# CH32V407VET-USB.net
KiCad netlist of a schematic drawn in Altium Designer
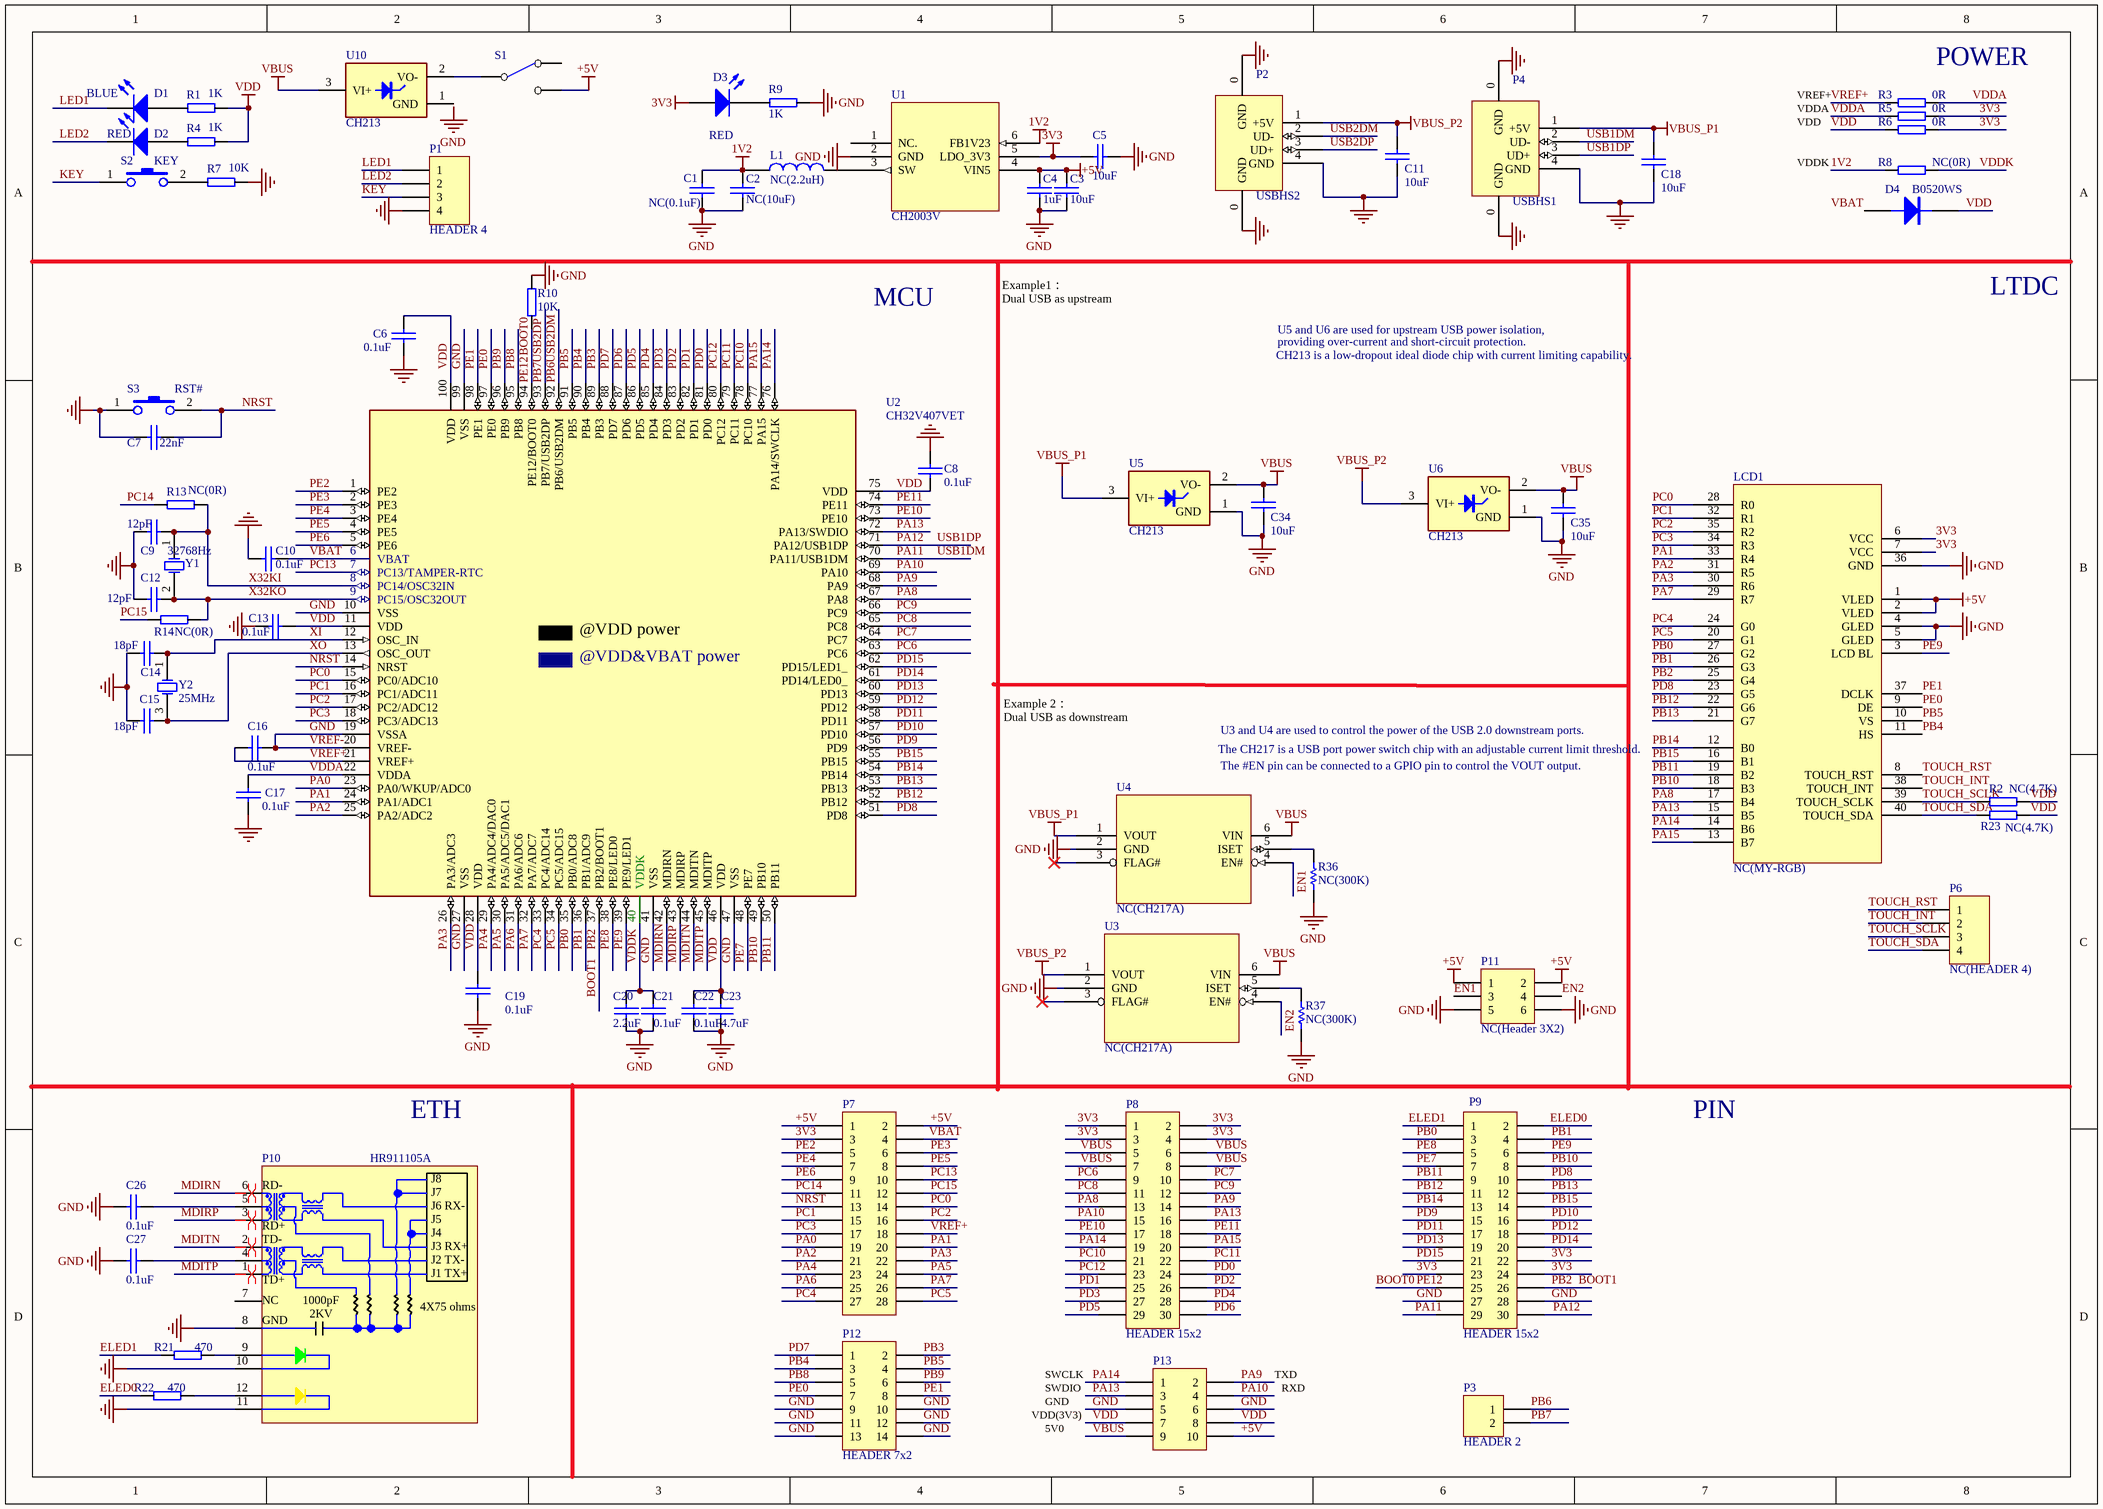
[diagram p0: CH32V407VET-USB.SchDoc]

(export (version "E")
  (design (tool "Eeschema 10.0.6"))
  (components
    (comp (ref "C1")
      (value "NC(0.1uF)")
      (footprint "0402_C")
      (description "Capacitor")
      (libsource (lib "") (part "CAP_1"))
    )
    (comp (ref "C2")
      (value "NC(10uF)")
      (footprint "0603_C")
      (description "Capacitor")
      (libsource (lib "*") (part "CAP"))
    )
    (comp (ref "C3")
      (value "10uF")
      (footprint "0603_C")
      (description "Capacitor")
      (libsource (lib "*") (part "CAP"))
    )
    (comp (ref "C4")
      (value "1uF")
      (footprint "0402_C")
      (description "Capacitor")
      (libsource (lib "") (part "CAP_1"))
    )
    (comp (ref "C5")
      (value "10uF")
      (footprint "0603_C")
      (description "Capacitor")
      (libsource (lib "*") (part "CAP"))
    )
    (comp (ref "C6")
      (value "0.1uF")
      (footprint "0402_C")
      (description "Capacitor")
      (libsource (lib "*") (part "CAP"))
    )
    (comp (ref "C7")
      (value "22nF")
      (footprint "0402_C")
      (description "Capacitor")
      (libsource (lib "") (part "CAP_2"))
    )
    (comp (ref "C8")
      (value "0.1uF")
      (footprint "0402_C")
      (description "Capacitor")
      (libsource (lib "*") (part "CAP"))
    )
    (comp (ref "C9")
      (value "12pF")
      (footprint "0402_C")
      (description "Capacitor")
      (libsource (lib "*") (part "CAP"))
    )
    (comp (ref "C10")
      (value "0.1uF")
      (footprint "0402_C")
      (description "Capacitor")
      (libsource (lib "*") (part "CAP"))
    )
    (comp (ref "C11")
      (value "10uF")
      (footprint "0603_C")
      (description "Capacitor")
      (libsource (lib "") (part "CAP_2"))
    )
    (comp (ref "C12")
      (value "12pF")
      (footprint "0402_C")
      (description "Capacitor")
      (libsource (lib "*") (part "CAP"))
    )
    (comp (ref "C13")
      (value "0.1uF")
      (footprint "0402_C")
      (description "Capacitor")
      (libsource (lib "*") (part "CAP"))
    )
    (comp (ref "C14")
      (value "18pF")
      (footprint "0402_C")
      (description "Capacitor")
      (libsource (lib "*") (part "CAP"))
    )
    (comp (ref "C15")
      (value "18pF")
      (footprint "0402_C")
      (description "Capacitor")
      (libsource (lib "*") (part "CAP"))
    )
    (comp (ref "C16")
      (value "0.1uF")
      (footprint "0402_C")
      (description "Capacitor")
      (libsource (lib "*") (part "CAP"))
    )
    (comp (ref "C17")
      (value "0.1uF")
      (footprint "0402_C")
      (description "Capacitor")
      (libsource (lib "*") (part "CAP"))
    )
    (comp (ref "C18")
      (value "10uF")
      (footprint "0603_C")
      (description "Capacitor")
      (libsource (lib "") (part "CAP_2"))
    )
    (comp (ref "C19")
      (value "0.1uF")
      (footprint "0402_C")
      (description "Capacitor")
      (libsource (lib "*") (part "CAP"))
    )
    (comp (ref "C20")
      (value "2.2uF")
      (footprint "0402_C")
      (description "Capacitor")
      (libsource (lib "*") (part "CAP"))
    )
    (comp (ref "C21")
      (value "0.1uF")
      (footprint "0402_C")
      (description "Capacitor")
      (libsource (lib "*") (part "CAP"))
    )
    (comp (ref "C22")
      (value "0.1uF")
      (footprint "0402_C")
      (description "Capacitor")
      (libsource (lib "*") (part "CAP"))
    )
    (comp (ref "C23")
      (value "4.7uF")
      (footprint "0402_C")
      (description "Capacitor")
      (libsource (lib "*") (part "CAP"))
    )
    (comp (ref "C26")
      (value "0.1uF")
      (footprint "0402_C")
      (description "Capacitor")
      (libsource (lib "wch_sch_others") (part "CAP"))
    )
    (comp (ref "C27")
      (value "0.1uF")
      (footprint "0402_C")
      (description "Capacitor")
      (libsource (lib "wch_sch_others") (part "CAP"))
    )
    (comp (ref "C34")
      (value "10uF")
      (footprint "0603_C")
      (description "Capacitor")
      (libsource (lib "") (part "CAP_2"))
    )
    (comp (ref "C35")
      (value "10uF")
      (footprint "0603_C")
      (description "Capacitor")
      (libsource (lib "") (part "CAP_2"))
    )
    (comp (ref "D1")
      (value "BLUE")
      (footprint "0603+")
      (description "Typical INFRARED GaAs LED")
      (fields (field (name "PUBLISHER") "Altium Limited"))
      (libsource (lib "*") (part "LED0"))
    )
    (comp (ref "D2")
      (value "RED")
      (footprint "0603+")
      (description "Typical INFRARED GaAs LED")
      (fields (field (name "PUBLISHER") "Altium Limited"))
      (libsource (lib "*") (part "LED0"))
    )
    (comp (ref "D3")
      (value "RED")
      (footprint "0603+")
      (description "Typical INFRARED GaAs LED")
      (fields (field (name "PUBLISHER") "Altium Limited"))
      (libsource (lib "*") (part "LED0"))
    )
    (comp (ref "D4")
      (value "B0520WS")
      (footprint "SOD-323")
      (description "Diode")
      (libsource (lib "*") (part "DIODE"))
    )
    (comp (ref "L1") (value "NC(2.2uH)") (footprint "CD32") (libsource (lib "*") (part "INDUCTOR")))
    (comp (ref "LCD1")
      (value "NC(MY-RGB)")
      (footprint "FPC40P-0.5-FK750M3")
      (libsource (lib "MY-显示") (part "MY-RGB"))
    )
    (comp (ref "P1")
      (value "HEADER 4")
      (footprint "SIP4-2.54mm")
      (description "Header, 4-Pin")
      (libsource (lib "wch_sch_others") (part "HEADER 4"))
    )
    (comp (ref "P2")
      (value "USBHS2")
      (footprint "USBAF")
      (description "USB Port")
      (libsource (lib "*") (part "USB"))
    )
    (comp (ref "P3")
      (value "HEADER 2")
      (footprint "MYPCB:SIP2-2.54mm")
      (description "Header, 2-Pin")
      (libsource (lib "wch_sch_others") (part "HEADER 2"))
    )
    (comp (ref "P4")
      (value "USBHS1")
      (footprint "USBAF")
      (description "USB Port")
      (libsource (lib "*") (part "USB"))
    )
    (comp (ref "P6")
      (value "NC(HEADER 4)")
      (footprint "SIP4-2.54mm")
      (description "Header, 4-Pin")
      (libsource (lib "wch_sch_others") (part "HEADER 4"))
    )
    (comp (ref "P7")
      (value "HEADER 14x2")
      (footprint "MYPCB:IDC28-2.54MM")
      (description "Header, 14-Pin, Dual row")
      (libsource (lib "wch_sch_others") (part "HEADER 14x2"))
    )
    (comp (ref "P8")
      (value "HEADER 15x2")
      (footprint "MYPCB:IDC30-2.54MM")
      (description "Header, 15-Pin, Dual row")
      (libsource (lib "wch_sch_others") (part "HEADER 15x2"))
    )
    (comp (ref "P9")
      (value "HEADER 15x2")
      (footprint "MYPCB:IDC30-2.54MM")
      (description "Header, 15-Pin, Dual row")
      (libsource (lib "wch_sch_others") (part "HEADER 15x2"))
    )
    (comp (ref "P10") (value "HR911105A") (footprint "HR911105A") (libsource (lib "*") (part "HR911105A")))
    (comp (ref "P11")
      (value "NC(Header 3X2)")
      (footprint "HDR2X3")
      (description "Header, 3-Pin, Dual row")
      (fields (field (name "PUBLISHER") "Altium Limited"))
      (libsource (lib "Miscellaneous Connectors") (part "Header 3X2"))
    )
    (comp (ref "P12")
      (value "HEADER 7x2")
      (footprint "MYPCB:IDC14-2.54mm")
      (description "Header, 7-Pin, Dual row")
      (libsource (lib "wch_sch_others") (part "HEADER 7x2"))
    )
    (comp (ref "P13")
      (value "LINK")
      (footprint "IDC10-2.54mm")
      (description "Header, 5-Pin, Dual row, Right Angle")
      (fields (field (name "PUBLISHER") "Altium Limited"))
      (libsource (lib "Miscellaneous Connectors") (part "Header 5X2H"))
    )
    (comp (ref "R1") (value "1K") (footprint "0402") (libsource (lib "wch_sch_others") (part "RES")))
    (comp (ref "R2") (value "NC(4.7K)") (footprint "0402") (libsource (lib "wch_sch_others") (part "RES")))
    (comp (ref "R3") (value "0R") (footprint "0402") (libsource (lib "*") (part "R")))
    (comp (ref "R4") (value "1K") (footprint "0402") (libsource (lib "wch_sch_others") (part "RES")))
    (comp (ref "R5") (value "0R") (footprint "0402") (libsource (lib "*") (part "R")))
    (comp (ref "R6") (value "0R") (footprint "0402") (libsource (lib "*") (part "R")))
    (comp (ref "R7") (value "10K") (footprint "0402") (libsource (lib "wch_sch_others") (part "RES")))
    (comp (ref "R8") (value "NC(0R)") (footprint "0402") (libsource (lib "*") (part "R")))
    (comp (ref "R9") (value "1K") (footprint "0402") (libsource (lib "wch_sch_others") (part "RES")))
    (comp (ref "R10") (value "10K") (footprint "0402") (libsource (lib "wch_sch_others") (part "RES")))
    (comp (ref "R13") (value "NC(0R)") (footprint "0402") (libsource (lib "wch_sch_others") (part "RES")))
    (comp (ref "R14") (value "NC(0R)") (footprint "0402") (libsource (lib "wch_sch_others") (part "RES")))
    (comp (ref "R21") (value "470") (footprint "0402") (libsource (lib "wch_sch_others") (part "RES")))
    (comp (ref "R22") (value "470") (footprint "0402") (libsource (lib "wch_sch_others") (part "RES")))
    (comp (ref "R23") (value "NC(4.7K)") (footprint "0402") (libsource (lib "wch_sch_others") (part "RES")))
    (comp (ref "R36")
      (value "NC(300K)")
      (footprint "0603")
      (description "Resistor")
      (fields (field (name "PUBLISHER") "Altium Limited"))
      (libsource (lib "MYLIB") (part "0603-1"))
    )
    (comp (ref "R37")
      (value "NC(300K)")
      (footprint "0603")
      (description "Resistor")
      (fields (field (name "PUBLISHER") "Altium Limited"))
      (libsource (lib "MYLIB") (part "0603-1"))
    )
    (comp (ref "S1") (value "SW SPDT") (footprint "SW1") (libsource (lib "*") (part "SW SPDT")))
    (comp (ref "S2")
      (value "KEY")
      (footprint "SMD_6.1x3.65x2.5mm-KEY")
      (libsource (lib "wch_sch_others") (part "KEY1"))
    )
    (comp (ref "S3")
      (value "RST#")
      (footprint "SMD_6.1x3.65x2.5mm-KEY")
      (libsource (lib "wch_sch_others") (part "KEY1"))
    )
    (comp (ref "U1")
      (value "CH2003V")
      (footprint "SOT-23-6")
      (description "Step-Down DC-DC Converter, 5V input, 1.23V * 800mA output, with LDO 3.3V * 200mA")
      (libsource (lib "CHXXX") (part "CH2003V"))
    )
    (comp (ref "U2")
      (value "CH32V407VET")
      (footprint "LQFP100")
      (description "RISC-V FPU HD-MCU, 175MHz, USB_480M, 100M Ethernet & Phy, CAN, DVP, ADC, DAC")
      (libsource (lib "CHXXX") (part "CH32V407VET"))
    )
    (comp (ref "U3")
      (value "NC(CH217A)")
      (footprint "SOT-23-6")
      (description "Current-Limited USB Power Distribution Switch")
      (libsource (lib "CHXXX") (part "CH217K"))
    )
    (comp (ref "U4")
      (value "NC(CH217A)")
      (footprint "SOT-23-6")
      (description "Current-Limited USB Power Distribution Switch")
      (libsource (lib "CHXXX") (part "CH217K"))
    )
    (comp (ref "U5")
      (value "CH213")
      (footprint "SOT-23-3")
      (description "Ideal Diode 5V*1A")
      (libsource (lib "CHXXX") (part "CH213E"))
    )
    (comp (ref "U6")
      (value "CH213")
      (footprint "SOT-23-3")
      (description "Ideal Diode 5V*1A")
      (libsource (lib "CHXXX") (part "CH213E"))
    )
    (comp (ref "U10")
      (value "CH213")
      (footprint "SOT-23-3")
      (description "Ideal Diode 5V*1A")
      (libsource (lib "CHXXX") (part "CH213E"))
    )
    (comp (ref "Y1")
      (value "32768Hz")
      (footprint "FC-135")
      (description "Crystal Oscillator")
      (fields (field (name "PUBLISHER") "Altium Limited"))
      (libsource (lib "*") (part "XTAL"))
    )
    (comp (ref "Y2")
      (value "25MHz")
      (footprint "XT3225")
      (description "Crystal Oscillator")
      (fields (field (name "PUBLISHER") "Altium Limited"))
      (libsource (lib "") (part "XTAL_1"))
    )
  )
  (nets
    (net (code "1") (name "+5V") (class "Default")
      (node (ref "C3") (pin "2") (pinfunction "2_2") (pintype "passive"))
      (node (ref "C4") (pin "2") (pinfunction "2_2") (pintype "passive"))
      (node (ref "LCD1") (pin "1") (pinfunction "VLED_1") (pintype "passive"))
      (node (ref "LCD1") (pin "2") (pinfunction "VLED_2") (pintype "passive"))
      (node (ref "P11") (pin "1") (pinfunction "1_1") (pintype "passive"))
      (node (ref "P11") (pin "2") (pinfunction "2_2") (pintype "passive"))
      (node (ref "P13") (pin "10") (pinfunction "10_10") (pintype "passive"))
      (node (ref "P7") (pin "1") (pinfunction "1_1") (pintype "passive"))
      (node (ref "P7") (pin "2") (pinfunction "2_2") (pintype "passive"))
      (node (ref "S1") (pin "2") (pinfunction "NC_2") (pintype "passive"))
      (node (ref "U1") (pin "4") (pinfunction "VIN5_4") (pintype "power_in"))
    )
    (net (code "3") (name "/BOOT0") (class "Default")
      (node (ref "P9") (pin "25") (pinfunction "25_25") (pintype "passive"))
      (node (ref "R10") (pin "2") (pintype "passive"))
      (node (ref "U2") (pin "94") (pinfunction "PE12/BOOT0_94") (pintype "bidirectional"))
    )
    (net (code "4") (name "/BOOT1") (class "Default")
      (node (ref "LCD1") (pin "25") (pinfunction "G4_25") (pintype "passive"))
      (node (ref "P9") (pin "26") (pinfunction "26_26") (pintype "passive"))
      (node (ref "U2") (pin "37") (pinfunction "PB2/BOOT1_37") (pintype "bidirectional"))
    )
    (net (code "5") (name "/ELED0") (class "Default")
      (node (ref "P9") (pin "2") (pinfunction "2_2") (pintype "passive"))
      (node (ref "R22") (pin "1") (pintype "passive"))
    )
    (net (code "6") (name "/ELED1") (class "Default")
      (node (ref "P9") (pin "1") (pinfunction "1_1") (pintype "passive"))
      (node (ref "R21") (pin "1") (pintype "passive"))
    )
    (net (code "7") (name "/EN1") (class "Default")
      (node (ref "P11") (pin "3") (pinfunction "3_3") (pintype "passive"))
      (node (ref "U4") (pin "4") (pinfunction "EN#_4") (pintype "input"))
    )
    (net (code "8") (name "/EN2") (class "Default")
      (node (ref "P11") (pin "4") (pinfunction "4_4") (pintype "passive"))
      (node (ref "U3") (pin "4") (pinfunction "EN#_4") (pintype "input"))
    )
    (net (code "9") (name "/KEY") (class "Default")
      (node (ref "P1") (pin "3") (pinfunction "3_3") (pintype "passive"))
      (node (ref "S2") (pin "1") (pinfunction "1_1") (pintype "passive"))
    )
    (net (code "10") (name "/LED1") (class "Default")
      (node (ref "D1") (pin "2") (pinfunction "K_2") (pintype "passive"))
      (node (ref "P1") (pin "1") (pinfunction "1_1") (pintype "passive"))
    )
    (net (code "11") (name "/LED2") (class "Default")
      (node (ref "D2") (pin "2") (pinfunction "K_2") (pintype "passive"))
      (node (ref "P1") (pin "2") (pinfunction "2_2") (pintype "passive"))
    )
    (net (code "12") (name "/MDIRN") (class "Default")
      (node (ref "P10") (pin "6") (pintype "passive"))
      (node (ref "U2") (pin "42") (pinfunction "MDIRN_42") (pintype "bidirectional"))
    )
    (net (code "13") (name "/MDIRP") (class "Default")
      (node (ref "P10") (pin "3") (pintype "passive"))
      (node (ref "U2") (pin "43") (pinfunction "MDIRP_43") (pintype "bidirectional"))
    )
    (net (code "14") (name "/MDITN") (class "Default")
      (node (ref "P10") (pin "2") (pintype "passive"))
      (node (ref "U2") (pin "44") (pinfunction "MDITN_44") (pintype "bidirectional"))
    )
    (net (code "15") (name "/MDITP") (class "Default")
      (node (ref "P10") (pin "1") (pintype "passive"))
      (node (ref "U2") (pin "45") (pinfunction "MDITP_45") (pintype "bidirectional"))
    )
    (net (code "16") (name "/NRST") (class "Default")
      (node (ref "C7") (pin "2") (pinfunction "2_2") (pintype "passive"))
      (node (ref "P7") (pin "13") (pinfunction "13_13") (pintype "passive"))
      (node (ref "S3") (pin "2") (pinfunction "2_2") (pintype "passive"))
      (node (ref "U2") (pin "14") (pinfunction "NRST_14") (pintype "input"))
    )
    (net (code "17") (name "/PA0") (class "Default")
      (node (ref "P7") (pin "19") (pinfunction "19_19") (pintype "passive"))
      (node (ref "U2") (pin "23") (pinfunction "PA0/WKUP/ADC0_23") (pintype "bidirectional"))
    )
    (net (code "18") (name "/PA1") (class "Default")
      (node (ref "LCD1") (pin "33") (pinfunction "R4_33") (pintype "passive"))
      (node (ref "P7") (pin "20") (pinfunction "20_20") (pintype "passive"))
      (node (ref "U2") (pin "24") (pinfunction "PA1/ADC1_24") (pintype "bidirectional"))
    )
    (net (code "19") (name "/PA2") (class "Default")
      (node (ref "LCD1") (pin "31") (pinfunction "R5_31") (pintype "passive"))
      (node (ref "P7") (pin "21") (pinfunction "21_21") (pintype "passive"))
      (node (ref "U2") (pin "25") (pinfunction "PA2/ADC2_25") (pintype "bidirectional"))
    )
    (net (code "20") (name "/PA3") (class "Default")
      (node (ref "LCD1") (pin "30") (pinfunction "R6_30") (pintype "passive"))
      (node (ref "P7") (pin "22") (pinfunction "22_22") (pintype "passive"))
      (node (ref "U2") (pin "26") (pinfunction "PA3/ADC3_26") (pintype "bidirectional"))
    )
    (net (code "21") (name "/PA4") (class "Default")
      (node (ref "P7") (pin "23") (pinfunction "23_23") (pintype "passive"))
      (node (ref "U2") (pin "29") (pinfunction "PA4/ADC4/DAC0_29") (pintype "bidirectional"))
    )
    (net (code "22") (name "/PA5") (class "Default")
      (node (ref "P7") (pin "24") (pinfunction "24_24") (pintype "passive"))
      (node (ref "U2") (pin "30") (pinfunction "PA5/ADC5/DAC1_30") (pintype "bidirectional"))
    )
    (net (code "23") (name "/PA6") (class "Default")
      (node (ref "P7") (pin "25") (pinfunction "25_25") (pintype "passive"))
      (node (ref "U2") (pin "31") (pinfunction "PA6/ADC6_31") (pintype "bidirectional"))
    )
    (net (code "24") (name "/PA7") (class "Default")
      (node (ref "LCD1") (pin "29") (pinfunction "R7_29") (pintype "passive"))
      (node (ref "P7") (pin "26") (pinfunction "26_26") (pintype "passive"))
      (node (ref "U2") (pin "32") (pinfunction "PA7/ADC7_32") (pintype "bidirectional"))
    )
    (net (code "25") (name "/PA8") (class "Default")
      (node (ref "LCD1") (pin "17") (pinfunction "B4_17") (pintype "passive"))
      (node (ref "P8") (pin "13") (pinfunction "13_13") (pintype "passive"))
      (node (ref "U2") (pin "67") (pinfunction "PA8_67") (pintype "bidirectional"))
    )
    (net (code "26") (name "/PA9") (class "Default")
      (node (ref "P13") (pin "2") (pinfunction "2_2") (pintype "passive"))
      (node (ref "P8") (pin "14") (pinfunction "14_14") (pintype "passive"))
      (node (ref "U2") (pin "68") (pinfunction "PA9_68") (pintype "bidirectional"))
    )
    (net (code "27") (name "/PA10") (class "Default")
      (node (ref "P13") (pin "4") (pinfunction "4_4") (pintype "passive"))
      (node (ref "P8") (pin "15") (pinfunction "15_15") (pintype "passive"))
      (node (ref "U2") (pin "69") (pinfunction "PA10_69") (pintype "bidirectional"))
    )
    (net (code "28") (name "/PA11") (class "Default")
      (node (ref "P4") (pin "2") (pinfunction "UD-_2") (pintype "bidirectional"))
      (node (ref "P9") (pin "29") (pinfunction "29_29") (pintype "passive"))
      (node (ref "U2") (pin "70") (pinfunction "PA11/USB1DM_70") (pintype "bidirectional"))
    )
    (net (code "29") (name "/PA12") (class "Default")
      (node (ref "P4") (pin "3") (pinfunction "UD+_3") (pintype "bidirectional"))
      (node (ref "P9") (pin "30") (pinfunction "30_30") (pintype "passive"))
      (node (ref "U2") (pin "71") (pinfunction "PA12/USB1DP_71") (pintype "bidirectional"))
    )
    (net (code "30") (name "/PA13") (class "Default")
      (node (ref "LCD1") (pin "15") (pinfunction "B5_15") (pintype "passive"))
      (node (ref "P13") (pin "3") (pinfunction "3_3") (pintype "passive"))
      (node (ref "P8") (pin "16") (pinfunction "16_16") (pintype "passive"))
      (node (ref "U2") (pin "72") (pinfunction "PA13/SWDIO_72") (pintype "bidirectional"))
    )
    (net (code "31") (name "/PA14") (class "Default")
      (node (ref "LCD1") (pin "14") (pinfunction "B6_14") (pintype "passive"))
      (node (ref "P13") (pin "1") (pinfunction "1_1") (pintype "passive"))
      (node (ref "P8") (pin "19") (pinfunction "19_19") (pintype "passive"))
      (node (ref "U2") (pin "76") (pinfunction "PA14/SWCLK_76") (pintype "bidirectional"))
    )
    (net (code "32") (name "/PA15") (class "Default")
      (node (ref "LCD1") (pin "13") (pinfunction "B7_13") (pintype "passive"))
      (node (ref "P8") (pin "20") (pinfunction "20_20") (pintype "passive"))
      (node (ref "U2") (pin "77") (pinfunction "PA15_77") (pintype "bidirectional"))
    )
    (net (code "33") (name "/PB0") (class "Default")
      (node (ref "LCD1") (pin "27") (pinfunction "G2_27") (pintype "passive"))
      (node (ref "P9") (pin "3") (pinfunction "3_3") (pintype "passive"))
      (node (ref "U2") (pin "35") (pinfunction "PB0/ADC8_35") (pintype "bidirectional"))
    )
    (net (code "34") (name "/PB1") (class "Default")
      (node (ref "LCD1") (pin "26") (pinfunction "G3_26") (pintype "passive"))
      (node (ref "P9") (pin "4") (pinfunction "4_4") (pintype "passive"))
      (node (ref "U2") (pin "36") (pinfunction "PB1/ADC9_36") (pintype "bidirectional"))
    )
    (net (code "35") (name "/PB3") (class "Default")
      (node (ref "P12") (pin "2") (pinfunction "2_2") (pintype "passive"))
      (node (ref "U2") (pin "89") (pinfunction "PB3_89") (pintype "bidirectional"))
    )
    (net (code "36") (name "/PB4") (class "Default")
      (node (ref "LCD1") (pin "11") (pinfunction "HS_11") (pintype "passive"))
      (node (ref "P12") (pin "3") (pinfunction "3_3") (pintype "passive"))
      (node (ref "U2") (pin "90") (pinfunction "PB4_90") (pintype "bidirectional"))
    )
    (net (code "37") (name "/PB5") (class "Default")
      (node (ref "LCD1") (pin "10") (pinfunction "VS_10") (pintype "passive"))
      (node (ref "P12") (pin "4") (pinfunction "4_4") (pintype "passive"))
      (node (ref "U2") (pin "91") (pinfunction "PB5_91") (pintype "bidirectional"))
    )
    (net (code "38") (name "/PB6") (class "Default")
      (node (ref "P2") (pin "2") (pinfunction "UD-_2") (pintype "bidirectional"))
      (node (ref "P3") (pin "1") (pinfunction "1_1") (pintype "passive"))
      (node (ref "U2") (pin "92") (pinfunction "PB6/USB2DM_92") (pintype "bidirectional"))
    )
    (net (code "39") (name "/PB7") (class "Default")
      (node (ref "P2") (pin "3") (pinfunction "UD+_3") (pintype "bidirectional"))
      (node (ref "P3") (pin "2") (pinfunction "2_2") (pintype "passive"))
      (node (ref "U2") (pin "93") (pinfunction "PB7/USB2DP_93") (pintype "bidirectional"))
    )
    (net (code "40") (name "/PB8") (class "Default")
      (node (ref "P12") (pin "5") (pinfunction "5_5") (pintype "passive"))
      (node (ref "U2") (pin "95") (pinfunction "PB8_95") (pintype "bidirectional"))
    )
    (net (code "41") (name "/PB9") (class "Default")
      (node (ref "P12") (pin "6") (pinfunction "6_6") (pintype "passive"))
      (node (ref "U2") (pin "96") (pinfunction "PB9_96") (pintype "bidirectional"))
    )
    (net (code "42") (name "/PB10") (class "Default")
      (node (ref "LCD1") (pin "18") (pinfunction "B3_18") (pintype "passive"))
      (node (ref "P9") (pin "8") (pinfunction "8_8") (pintype "passive"))
      (node (ref "U2") (pin "49") (pinfunction "PB10_49") (pintype "bidirectional"))
    )
    (net (code "43") (name "/PB11") (class "Default")
      (node (ref "LCD1") (pin "19") (pinfunction "B2_19") (pintype "passive"))
      (node (ref "P9") (pin "9") (pinfunction "9_9") (pintype "passive"))
      (node (ref "U2") (pin "50") (pinfunction "PB11_50") (pintype "bidirectional"))
    )
    (net (code "44") (name "/PB12") (class "Default")
      (node (ref "LCD1") (pin "22") (pinfunction "G6_22") (pintype "passive"))
      (node (ref "P9") (pin "11") (pinfunction "11_11") (pintype "passive"))
      (node (ref "U2") (pin "52") (pinfunction "PB12_52") (pintype "bidirectional"))
    )
    (net (code "45") (name "/PB13") (class "Default")
      (node (ref "LCD1") (pin "21") (pinfunction "G7_21") (pintype "passive"))
      (node (ref "P9") (pin "12") (pinfunction "12_12") (pintype "passive"))
      (node (ref "U2") (pin "53") (pinfunction "PB13_53") (pintype "bidirectional"))
    )
    (net (code "46") (name "/PB14") (class "Default")
      (node (ref "LCD1") (pin "12") (pinfunction "B0_12") (pintype "passive"))
      (node (ref "P9") (pin "13") (pinfunction "13_13") (pintype "passive"))
      (node (ref "U2") (pin "54") (pinfunction "PB14_54") (pintype "bidirectional"))
    )
    (net (code "47") (name "/PB15") (class "Default")
      (node (ref "LCD1") (pin "16") (pinfunction "B1_16") (pintype "passive"))
      (node (ref "P9") (pin "14") (pinfunction "14_14") (pintype "passive"))
      (node (ref "U2") (pin "55") (pinfunction "PB15_55") (pintype "bidirectional"))
    )
    (net (code "48") (name "/PC0") (class "Default")
      (node (ref "LCD1") (pin "28") (pinfunction "R0_28") (pintype "passive"))
      (node (ref "P7") (pin "14") (pinfunction "14_14") (pintype "passive"))
      (node (ref "U2") (pin "15") (pinfunction "PC0/ADC10_15") (pintype "bidirectional"))
    )
    (net (code "49") (name "/PC1") (class "Default")
      (node (ref "LCD1") (pin "32") (pinfunction "R1_32") (pintype "passive"))
      (node (ref "P7") (pin "15") (pinfunction "15_15") (pintype "passive"))
      (node (ref "U2") (pin "16") (pinfunction "PC1/ADC11_16") (pintype "bidirectional"))
    )
    (net (code "50") (name "/PC2") (class "Default")
      (node (ref "LCD1") (pin "35") (pinfunction "R2_35") (pintype "passive"))
      (node (ref "P7") (pin "16") (pinfunction "16_16") (pintype "passive"))
      (node (ref "U2") (pin "17") (pinfunction "PC2/ADC12_17") (pintype "bidirectional"))
    )
    (net (code "51") (name "/PC3") (class "Default")
      (node (ref "LCD1") (pin "34") (pinfunction "R3_34") (pintype "passive"))
      (node (ref "P7") (pin "17") (pinfunction "17_17") (pintype "passive"))
      (node (ref "U2") (pin "18") (pinfunction "PC3/ADC13_18") (pintype "bidirectional"))
    )
    (net (code "52") (name "/PC4") (class "Default")
      (node (ref "LCD1") (pin "24") (pinfunction "G0_24") (pintype "passive"))
      (node (ref "P7") (pin "27") (pinfunction "27_27") (pintype "passive"))
      (node (ref "U2") (pin "33") (pinfunction "PC4/ADC14_33") (pintype "bidirectional"))
    )
    (net (code "53") (name "/PC5") (class "Default")
      (node (ref "LCD1") (pin "20") (pinfunction "G1_20") (pintype "passive"))
      (node (ref "P7") (pin "28") (pinfunction "28_28") (pintype "passive"))
      (node (ref "U2") (pin "34") (pinfunction "PC5/ADC15_34") (pintype "bidirectional"))
    )
    (net (code "54") (name "/PC6") (class "Default")
      (node (ref "P8") (pin "9") (pinfunction "9_9") (pintype "passive"))
      (node (ref "U2") (pin "63") (pinfunction "PC6_63") (pintype "bidirectional"))
    )
    (net (code "55") (name "/PC7") (class "Default")
      (node (ref "P8") (pin "10") (pinfunction "10_10") (pintype "passive"))
      (node (ref "U2") (pin "64") (pinfunction "PC7_64") (pintype "bidirectional"))
    )
    (net (code "56") (name "/PC8") (class "Default")
      (node (ref "P8") (pin "11") (pinfunction "11_11") (pintype "passive"))
      (node (ref "U2") (pin "65") (pinfunction "PC8_65") (pintype "bidirectional"))
    )
    (net (code "57") (name "/PC9") (class "Default")
      (node (ref "P8") (pin "12") (pinfunction "12_12") (pintype "passive"))
      (node (ref "U2") (pin "66") (pinfunction "PC9_66") (pintype "bidirectional"))
    )
    (net (code "58") (name "/PC10") (class "Default")
      (node (ref "P8") (pin "21") (pinfunction "21_21") (pintype "passive"))
      (node (ref "U2") (pin "78") (pinfunction "PC10_78") (pintype "bidirectional"))
    )
    (net (code "59") (name "/PC11") (class "Default")
      (node (ref "P8") (pin "22") (pinfunction "22_22") (pintype "passive"))
      (node (ref "U2") (pin "79") (pinfunction "PC11_79") (pintype "bidirectional"))
    )
    (net (code "60") (name "/PC12") (class "Default")
      (node (ref "P8") (pin "23") (pinfunction "23_23") (pintype "passive"))
      (node (ref "U2") (pin "80") (pinfunction "PC12_80") (pintype "bidirectional"))
    )
    (net (code "61") (name "/PC13") (class "Default")
      (node (ref "P7") (pin "10") (pinfunction "10_10") (pintype "passive"))
      (node (ref "U2") (pin "7") (pinfunction "PC13/TAMPER-RTC_7") (pintype "bidirectional"))
    )
    (net (code "62") (name "/PC14") (class "Default")
      (node (ref "P7") (pin "11") (pinfunction "11_11") (pintype "passive"))
      (node (ref "R13") (pin "1") (pintype "passive"))
    )
    (net (code "63") (name "/PC15") (class "Default")
      (node (ref "P7") (pin "12") (pinfunction "12_12") (pintype "passive"))
      (node (ref "R14") (pin "1") (pintype "passive"))
    )
    (net (code "64") (name "/PD0") (class "Default")
      (node (ref "P8") (pin "24") (pinfunction "24_24") (pintype "passive"))
      (node (ref "U2") (pin "81") (pinfunction "PD0_81") (pintype "bidirectional"))
    )
    (net (code "65") (name "/PD1") (class "Default")
      (node (ref "P8") (pin "25") (pinfunction "25_25") (pintype "passive"))
      (node (ref "U2") (pin "82") (pinfunction "PD1_82") (pintype "bidirectional"))
    )
    (net (code "66") (name "/PD2") (class "Default")
      (node (ref "P8") (pin "26") (pinfunction "26_26") (pintype "passive"))
      (node (ref "U2") (pin "83") (pinfunction "PD2_83") (pintype "bidirectional"))
    )
    (net (code "67") (name "/PD3") (class "Default")
      (node (ref "P8") (pin "27") (pinfunction "27_27") (pintype "passive"))
      (node (ref "U2") (pin "84") (pinfunction "PD3_84") (pintype "bidirectional"))
    )
    (net (code "68") (name "/PD4") (class "Default")
      (node (ref "P8") (pin "28") (pinfunction "28_28") (pintype "passive"))
      (node (ref "U2") (pin "85") (pinfunction "PD4_85") (pintype "bidirectional"))
    )
    (net (code "69") (name "/PD5") (class "Default")
      (node (ref "P8") (pin "29") (pinfunction "29_29") (pintype "passive"))
      (node (ref "U2") (pin "86") (pinfunction "PD5_86") (pintype "bidirectional"))
    )
    (net (code "70") (name "/PD6") (class "Default")
      (node (ref "P8") (pin "30") (pinfunction "30_30") (pintype "passive"))
      (node (ref "U2") (pin "87") (pinfunction "PD6_87") (pintype "bidirectional"))
    )
    (net (code "71") (name "/PD7") (class "Default")
      (node (ref "P12") (pin "1") (pinfunction "1_1") (pintype "passive"))
      (node (ref "U2") (pin "88") (pinfunction "PD7_88") (pintype "bidirectional"))
    )
    (net (code "72") (name "/PD8") (class "Default")
      (node (ref "LCD1") (pin "23") (pinfunction "G5_23") (pintype "passive"))
      (node (ref "P9") (pin "10") (pinfunction "10_10") (pintype "passive"))
      (node (ref "U2") (pin "51") (pinfunction "PD8_51") (pintype "bidirectional"))
    )
    (net (code "73") (name "/PD9") (class "Default")
      (node (ref "P9") (pin "15") (pinfunction "15_15") (pintype "passive"))
      (node (ref "U2") (pin "56") (pinfunction "PD9_56") (pintype "bidirectional"))
    )
    (net (code "74") (name "/PD10") (class "Default")
      (node (ref "P9") (pin "16") (pinfunction "16_16") (pintype "passive"))
      (node (ref "U2") (pin "57") (pinfunction "PD10_57") (pintype "bidirectional"))
    )
    (net (code "75") (name "/PD11") (class "Default")
      (node (ref "P9") (pin "17") (pinfunction "17_17") (pintype "passive"))
      (node (ref "U2") (pin "58") (pinfunction "PD11_58") (pintype "bidirectional"))
    )
    (net (code "76") (name "/PD12") (class "Default")
      (node (ref "P9") (pin "18") (pinfunction "18_18") (pintype "passive"))
      (node (ref "U2") (pin "59") (pinfunction "PD12_59") (pintype "bidirectional"))
    )
    (net (code "77") (name "/PD13") (class "Default")
      (node (ref "P9") (pin "19") (pinfunction "19_19") (pintype "passive"))
      (node (ref "U2") (pin "60") (pinfunction "PD13_60") (pintype "bidirectional"))
    )
    (net (code "78") (name "/PD14") (class "Default")
      (node (ref "P9") (pin "20") (pinfunction "20_20") (pintype "passive"))
      (node (ref "U2") (pin "61") (pinfunction "PD14/LED0__61") (pintype "bidirectional"))
    )
    (net (code "79") (name "/PD15") (class "Default")
      (node (ref "P9") (pin "21") (pinfunction "21_21") (pintype "passive"))
      (node (ref "U2") (pin "62") (pinfunction "PD15/LED1__62") (pintype "bidirectional"))
    )
    (net (code "80") (name "/PE0") (class "Default")
      (node (ref "LCD1") (pin "9") (pinfunction "DE_9") (pintype "passive"))
      (node (ref "P12") (pin "7") (pinfunction "7_7") (pintype "passive"))
      (node (ref "U2") (pin "97") (pinfunction "PE0_97") (pintype "bidirectional"))
    )
    (net (code "81") (name "/PE1") (class "Default")
      (node (ref "LCD1") (pin "37") (pinfunction "DCLK_37") (pintype "passive"))
      (node (ref "P12") (pin "8") (pinfunction "8_8") (pintype "passive"))
      (node (ref "U2") (pin "98") (pinfunction "PE1_98") (pintype "bidirectional"))
    )
    (net (code "82") (name "/PE2") (class "Default")
      (node (ref "P7") (pin "5") (pinfunction "5_5") (pintype "passive"))
      (node (ref "U2") (pin "1") (pinfunction "PE2_1") (pintype "bidirectional"))
    )
    (net (code "83") (name "/PE3") (class "Default")
      (node (ref "P7") (pin "6") (pinfunction "6_6") (pintype "passive"))
      (node (ref "U2") (pin "2") (pinfunction "PE3_2") (pintype "bidirectional"))
    )
    (net (code "84") (name "/PE4") (class "Default")
      (node (ref "P7") (pin "7") (pinfunction "7_7") (pintype "passive"))
      (node (ref "U2") (pin "3") (pinfunction "PE4_3") (pintype "bidirectional"))
    )
    (net (code "85") (name "/PE5") (class "Default")
      (node (ref "P7") (pin "8") (pinfunction "8_8") (pintype "passive"))
      (node (ref "U2") (pin "4") (pinfunction "PE5_4") (pintype "bidirectional"))
    )
    (net (code "86") (name "/PE6") (class "Default")
      (node (ref "P7") (pin "9") (pinfunction "9_9") (pintype "passive"))
      (node (ref "U2") (pin "5") (pinfunction "PE6_5") (pintype "bidirectional"))
    )
    (net (code "87") (name "/PE7") (class "Default")
      (node (ref "P9") (pin "7") (pinfunction "7_7") (pintype "passive"))
      (node (ref "U2") (pin "48") (pinfunction "PE7_48") (pintype "bidirectional"))
    )
    (net (code "88") (name "/PE8") (class "Default")
      (node (ref "P9") (pin "5") (pinfunction "5_5") (pintype "passive"))
      (node (ref "U2") (pin "38") (pinfunction "PE8/LED0_38") (pintype "bidirectional"))
    )
    (net (code "89") (name "/PE9") (class "Default")
      (node (ref "LCD1") (pin "3") (pinfunction "LCD_BL_3") (pintype "passive"))
      (node (ref "P9") (pin "6") (pinfunction "6_6") (pintype "passive"))
      (node (ref "U2") (pin "39") (pinfunction "PE9/LED1_39") (pintype "bidirectional"))
    )
    (net (code "90") (name "/PE10") (class "Default")
      (node (ref "P8") (pin "17") (pinfunction "17_17") (pintype "passive"))
      (node (ref "U2") (pin "73") (pinfunction "PE10_73") (pintype "bidirectional"))
    )
    (net (code "91") (name "/PE11") (class "Default")
      (node (ref "P8") (pin "18") (pinfunction "18_18") (pintype "passive"))
      (node (ref "U2") (pin "74") (pinfunction "PE11_74") (pintype "bidirectional"))
    )
    (net (code "92") (name "/TOUCH_INT") (class "Default")
      (node (ref "LCD1") (pin "38") (pinfunction "TOUCH_INT_38") (pintype "passive"))
      (node (ref "P6") (pin "2") (pinfunction "2_2") (pintype "passive"))
    )
    (net (code "93") (name "/TOUCH_RST") (class "Default")
      (node (ref "LCD1") (pin "8") (pinfunction "TOUCH_RST_8") (pintype "passive"))
      (node (ref "P6") (pin "1") (pinfunction "1_1") (pintype "passive"))
    )
    (net (code "94") (name "/TOUCH_SCLK") (class "Default")
      (node (ref "LCD1") (pin "39") (pinfunction "TOUCH_SCLK_39") (pintype "passive"))
      (node (ref "P6") (pin "3") (pinfunction "3_3") (pintype "passive"))
      (node (ref "R2") (pin "2") (pintype "passive"))
    )
    (net (code "95") (name "/TOUCH_SDA") (class "Default")
      (node (ref "LCD1") (pin "40") (pinfunction "TOUCH_SDA_40") (pintype "passive"))
      (node (ref "P6") (pin "4") (pinfunction "4_4") (pintype "passive"))
      (node (ref "R23") (pin "2") (pintype "passive"))
    )
    (net (code "96") (name "/VBAT") (class "Default")
      (node (ref "C10") (pin "2") (pinfunction "2_2") (pintype "passive"))
      (node (ref "P7") (pin "4") (pinfunction "4_4") (pintype "passive"))
      (node (ref "U2") (pin "6") (pinfunction "VBAT_6") (pintype "power_in"))
    )
    (net (code "97") (name "/VDDA") (class "Default")
      (node (ref "C17") (pin "1") (pinfunction "1_1") (pintype "passive"))
      (node (ref "R3") (pin "1") (pinfunction "1_1") (pintype "passive"))
      (node (ref "R5") (pin "2") (pinfunction "2_2") (pintype "passive"))
      (node (ref "U2") (pin "22") (pinfunction "VDDA_22") (pintype "power_in"))
    )
    (net (code "98") (name "/VDDK") (class "Default")
      (node (ref "C20") (pin "2") (pinfunction "2_2") (pintype "passive"))
      (node (ref "C21") (pin "2") (pinfunction "2_2") (pintype "passive"))
      (node (ref "R8") (pin "1") (pinfunction "1_1") (pintype "passive"))
      (node (ref "U2") (pin "40") (pinfunction "VDDK_40") (pintype "power_in"))
    )
    (net (code "99") (name "/VREF+") (class "Default")
      (node (ref "C16") (pin "1") (pinfunction "1_1") (pintype "passive"))
      (node (ref "P7") (pin "18") (pinfunction "18_18") (pintype "passive"))
      (node (ref "R3") (pin "2") (pinfunction "2_2") (pintype "passive"))
      (node (ref "U2") (pin "21") (pinfunction "VREF+_21") (pintype "power_in"))
    )
    (net (code "100") (name "/X32KI") (class "Default")
      (node (ref "C9") (pin "2") (pinfunction "2_2") (pintype "passive"))
      (node (ref "R13") (pin "2") (pintype "passive"))
      (node (ref "U2") (pin "8") (pinfunction "PC14/OSC32IN_8") (pintype "bidirectional"))
      (node (ref "Y1") (pin "1") (pinfunction "OSC1_1") (pintype "passive"))
    )
    (net (code "101") (name "/X32KO") (class "Default")
      (node (ref "C12") (pin "2") (pinfunction "2_2") (pintype "passive"))
      (node (ref "R14") (pin "2") (pintype "passive"))
      (node (ref "U2") (pin "9") (pinfunction "PC15/OSC32OUT_9") (pintype "bidirectional"))
      (node (ref "Y1") (pin "2") (pinfunction "OSC2_2") (pintype "passive"))
    )
    (net (code "102") (name "/XI") (class "Default")
      (node (ref "C14") (pin "2") (pinfunction "2_2") (pintype "passive"))
      (node (ref "U2") (pin "12") (pinfunction "OSC_IN_12") (pintype "input"))
      (node (ref "Y2") (pin "1") (pinfunction "OSC1_1") (pintype "passive"))
    )
    (net (code "103") (name "/XO") (class "Default")
      (node (ref "C15") (pin "2") (pinfunction "2_2") (pintype "passive"))
      (node (ref "U2") (pin "13") (pinfunction "OSC_OUT_13") (pintype "output"))
      (node (ref "Y2") (pin "3") (pinfunction "OSC2_3") (pintype "passive"))
    )
    (net (code "104") (name "1V2") (class "Default")
      (node (ref "C1") (pin "2") (pinfunction "2_2") (pintype "passive"))
      (node (ref "C2") (pin "2") (pinfunction "2_2") (pintype "passive"))
      (node (ref "L1") (pin "2") (pinfunction "2_2") (pintype "passive"))
      (node (ref "R8") (pin "2") (pinfunction "2_2") (pintype "passive"))
      (node (ref "U1") (pin "6") (pinfunction "FB1V23_6") (pintype "input"))
    )
    (net (code "105") (name "3V3") (class "Default")
      (node (ref "C5") (pin "2") (pinfunction "2_2") (pintype "passive"))
      (node (ref "D3") (pin "1") (pinfunction "A_1") (pintype "passive"))
      (node (ref "LCD1") (pin "6") (pinfunction "VCC_6") (pintype "passive"))
      (node (ref "LCD1") (pin "7") (pinfunction "VCC_7") (pintype "passive"))
      (node (ref "P7") (pin "3") (pinfunction "3_3") (pintype "passive"))
      (node (ref "P8") (pin "1") (pinfunction "1_1") (pintype "passive"))
      (node (ref "P8") (pin "2") (pinfunction "2_2") (pintype "passive"))
      (node (ref "P8") (pin "3") (pinfunction "3_3") (pintype "passive"))
      (node (ref "P8") (pin "4") (pinfunction "4_4") (pintype "passive"))
      (node (ref "P9") (pin "22") (pinfunction "22_22") (pintype "passive"))
      (node (ref "P9") (pin "23") (pinfunction "23_23") (pintype "passive"))
      (node (ref "P9") (pin "24") (pinfunction "24_24") (pintype "passive"))
      (node (ref "R5") (pin "1") (pinfunction "1_1") (pintype "passive"))
      (node (ref "R6") (pin "1") (pinfunction "1_1") (pintype "passive"))
      (node (ref "U1") (pin "5") (pinfunction "LDO_3V3_5") (pintype "power_in"))
    )
    (net (code "106") (name "GND") (class "Default")
      (node (ref "C1") (pin "1") (pinfunction "1_1") (pintype "passive"))
      (node (ref "C10") (pin "1") (pinfunction "1_1") (pintype "passive"))
      (node (ref "C11") (pin "2") (pinfunction "2_2") (pintype "passive"))
      (node (ref "C12") (pin "1") (pinfunction "1_1") (pintype "passive"))
      (node (ref "C13") (pin "2") (pinfunction "2_2") (pintype "passive"))
      (node (ref "C14") (pin "1") (pinfunction "1_1") (pintype "passive"))
      (node (ref "C15") (pin "1") (pinfunction "1_1") (pintype "passive"))
      (node (ref "C16") (pin "2") (pinfunction "2_2") (pintype "passive"))
      (node (ref "C17") (pin "2") (pinfunction "2_2") (pintype "passive"))
      (node (ref "C18") (pin "2") (pinfunction "2_2") (pintype "passive"))
      (node (ref "C19") (pin "1") (pinfunction "1_1") (pintype "passive"))
      (node (ref "C2") (pin "1") (pinfunction "1_1") (pintype "passive"))
      (node (ref "C20") (pin "1") (pinfunction "1_1") (pintype "passive"))
      (node (ref "C21") (pin "1") (pinfunction "1_1") (pintype "passive"))
      (node (ref "C22") (pin "1") (pinfunction "1_1") (pintype "passive"))
      (node (ref "C23") (pin "1") (pinfunction "1_1") (pintype "passive"))
      (node (ref "C26") (pin "1") (pinfunction "1_1") (pintype "passive"))
      (node (ref "C27") (pin "1") (pinfunction "1_1") (pintype "passive"))
      (node (ref "C3") (pin "1") (pinfunction "1_1") (pintype "passive"))
      (node (ref "C34") (pin "2") (pinfunction "2_2") (pintype "passive"))
      (node (ref "C35") (pin "2") (pinfunction "2_2") (pintype "passive"))
      (node (ref "C4") (pin "1") (pinfunction "1_1") (pintype "passive"))
      (node (ref "C5") (pin "1") (pinfunction "1_1") (pintype "passive"))
      (node (ref "C6") (pin "1") (pinfunction "1_1") (pintype "passive"))
      (node (ref "C7") (pin "1") (pinfunction "1_1") (pintype "passive"))
      (node (ref "C8") (pin "2") (pinfunction "2_2") (pintype "passive"))
      (node (ref "C9") (pin "1") (pinfunction "1_1") (pintype "passive"))
      (node (ref "LCD1") (pin "36") (pinfunction "GND_36") (pintype "passive"))
      (node (ref "LCD1") (pin "4") (pinfunction "GLED_4") (pintype "passive"))
      (node (ref "LCD1") (pin "5") (pinfunction "GLED_5") (pintype "passive"))
      (node (ref "P1") (pin "4") (pinfunction "4_4") (pintype "passive"))
      (node (ref "P10") (pin "10") (pintype "passive"))
      (node (ref "P10") (pin "11") (pintype "passive"))
      (node (ref "P10") (pin "8") (pintype "passive"))
      (node (ref "P11") (pin "5") (pinfunction "5_5") (pintype "passive"))
      (node (ref "P11") (pin "6") (pinfunction "6_6") (pintype "passive"))
      (node (ref "P12") (pin "10") (pinfunction "10_10") (pintype "passive"))
      (node (ref "P12") (pin "11") (pinfunction "11_11") (pintype "passive"))
      (node (ref "P12") (pin "12") (pinfunction "12_12") (pintype "passive"))
      (node (ref "P12") (pin "13") (pinfunction "13_13") (pintype "passive"))
      (node (ref "P12") (pin "14") (pinfunction "14_14") (pintype "passive"))
      (node (ref "P12") (pin "9") (pinfunction "9_9") (pintype "passive"))
      (node (ref "P13") (pin "5") (pinfunction "5_5") (pintype "passive"))
      (node (ref "P13") (pin "6") (pinfunction "6_6") (pintype "passive"))
      (node (ref "P2") (pin "0") (pinfunction "GND_0") (pintype "power_in"))
      (node (ref "P2") (pin "4") (pinfunction "GND_4") (pintype "power_in"))
      (node (ref "P4") (pin "0") (pinfunction "GND_0") (pintype "power_in"))
      (node (ref "P4") (pin "4") (pinfunction "GND_4") (pintype "power_in"))
      (node (ref "P9") (pin "27") (pinfunction "27_27") (pintype "passive"))
      (node (ref "P9") (pin "28") (pinfunction "28_28") (pintype "passive"))
      (node (ref "R10") (pin "1") (pintype "passive"))
      (node (ref "R36") (pin "2") (pinfunction "2_2") (pintype "passive"))
      (node (ref "R37") (pin "2") (pinfunction "2_2") (pintype "passive"))
      (node (ref "R7") (pin "1") (pintype "passive"))
      (node (ref "R9") (pin "2") (pintype "passive"))
      (node (ref "S3") (pin "1") (pinfunction "1_1") (pintype "passive"))
      (node (ref "U1") (pin "2") (pinfunction "GND_2") (pintype "power_in"))
      (node (ref "U2") (pin "10") (pinfunction "VSS_10") (pintype "power_in"))
      (node (ref "U2") (pin "19") (pinfunction "VSSA_19") (pintype "power_in"))
      (node (ref "U2") (pin "20") (pinfunction "VREF-_20") (pintype "power_in"))
      (node (ref "U2") (pin "27") (pinfunction "VSS_27") (pintype "power_in"))
      (node (ref "U2") (pin "41") (pinfunction "VSS_41") (pintype "power_in"))
      (node (ref "U2") (pin "47") (pinfunction "VSS_47") (pintype "power_in"))
      (node (ref "U2") (pin "99") (pinfunction "VSS_99") (pintype "power_in"))
      (node (ref "U3") (pin "2") (pinfunction "GND_2") (pintype "power_in"))
      (node (ref "U4") (pin "2") (pinfunction "GND_2") (pintype "power_in"))
      (node (ref "U5") (pin "1") (pinfunction "GND_1") (pintype "power_in"))
      (node (ref "U6") (pin "1") (pinfunction "GND_1") (pintype "power_in"))
    )
    (net (code "107") (name "Net-(C26-Pad2)") (class "Default")
      (node (ref "C26") (pin "2") (pinfunction "2_2") (pintype "passive"))
      (node (ref "P10") (pin "5") (pintype "passive"))
    )
    (net (code "108") (name "Net-(C27-Pad2)") (class "Default")
      (node (ref "C27") (pin "2") (pinfunction "2_2") (pintype "passive"))
      (node (ref "P10") (pin "4") (pintype "passive"))
    )
    (net (code "109") (name "Net-(D1-A)") (class "Default")
      (node (ref "D1") (pin "1") (pinfunction "A_1") (pintype "passive"))
      (node (ref "R1") (pin "2") (pintype "passive"))
    )
    (net (code "110") (name "Net-(D2-A)") (class "Default")
      (node (ref "D2") (pin "1") (pinfunction "A_1") (pintype "passive"))
      (node (ref "R4") (pin "2") (pintype "passive"))
    )
    (net (code "111") (name "Net-(D3-K)") (class "Default")
      (node (ref "D3") (pin "2") (pinfunction "K_2") (pintype "passive"))
      (node (ref "R9") (pin "1") (pintype "passive"))
    )
    (net (code "112") (name "Net-(P10-Pad9)") (class "Default")
      (node (ref "P10") (pin "9") (pintype "passive"))
      (node (ref "R21") (pin "2") (pintype "passive"))
    )
    (net (code "113") (name "Net-(P10-Pad12)") (class "Default")
      (node (ref "P10") (pin "12") (pintype "passive"))
      (node (ref "R22") (pin "2") (pintype "passive"))
    )
    (net (code "114") (name "Net-(R7-Pad2)") (class "Default")
      (node (ref "R7") (pin "2") (pintype "passive"))
      (node (ref "S2") (pin "2") (pinfunction "2_2") (pintype "passive"))
    )
    (net (code "115") (name "Net-(S1-COMMON)") (class "Default")
      (node (ref "S1") (pin "1") (pinfunction "COMMON_1") (pintype "passive"))
      (node (ref "U10") (pin "2") (pinfunction "VO-_2") (pintype "power_in"))
    )
    (net (code "116") (name "Net-(U1-SW)") (class "Default")
      (node (ref "L1") (pin "1") (pinfunction "1_1") (pintype "passive"))
      (node (ref "U1") (pin "3") (pinfunction "SW_3") (pintype "output"))
    )
    (net (code "117") (name "Net-(U3-ISET)") (class "Default")
      (node (ref "R37") (pin "1") (pinfunction "1_1") (pintype "passive"))
      (node (ref "U3") (pin "5") (pinfunction "ISET_5") (pintype "bidirectional"))
    )
    (net (code "118") (name "Net-(U4-ISET)") (class "Default")
      (node (ref "R36") (pin "1") (pinfunction "1_1") (pintype "passive"))
      (node (ref "U4") (pin "5") (pinfunction "ISET_5") (pintype "bidirectional"))
    )
    (net (code "119") (name "VBUS") (class "Default")
      (node (ref "C34") (pin "1") (pinfunction "1_1") (pintype "passive"))
      (node (ref "C35") (pin "1") (pinfunction "1_1") (pintype "passive"))
      (node (ref "P13") (pin "9") (pinfunction "9_9") (pintype "passive"))
      (node (ref "P8") (pin "5") (pinfunction "5_5") (pintype "passive"))
      (node (ref "P8") (pin "6") (pinfunction "6_6") (pintype "passive"))
      (node (ref "P8") (pin "7") (pinfunction "7_7") (pintype "passive"))
      (node (ref "P8") (pin "8") (pinfunction "8_8") (pintype "passive"))
      (node (ref "U10") (pin "3") (pinfunction "VI+_3") (pintype "power_in"))
      (node (ref "U3") (pin "6") (pinfunction "VIN_6") (pintype "power_in"))
      (node (ref "U4") (pin "6") (pinfunction "VIN_6") (pintype "power_in"))
      (node (ref "U5") (pin "2") (pinfunction "VO-_2") (pintype "power_in"))
      (node (ref "U6") (pin "2") (pinfunction "VO-_2") (pintype "power_in"))
    )
    (net (code "120") (name "VBUS_P1") (class "Default")
      (node (ref "C18") (pin "1") (pinfunction "1_1") (pintype "passive"))
      (node (ref "P4") (pin "1") (pinfunction "+5V_1") (pintype "power_in"))
      (node (ref "U4") (pin "1") (pinfunction "VOUT_1") (pintype "power_in"))
      (node (ref "U5") (pin "3") (pinfunction "VI+_3") (pintype "power_in"))
    )
    (net (code "121") (name "VBUS_P2") (class "Default")
      (node (ref "C11") (pin "1") (pinfunction "1_1") (pintype "passive"))
      (node (ref "P2") (pin "1") (pinfunction "+5V_1") (pintype "power_in"))
      (node (ref "U3") (pin "1") (pinfunction "VOUT_1") (pintype "power_in"))
      (node (ref "U6") (pin "3") (pinfunction "VI+_3") (pintype "power_in"))
    )
    (net (code "122") (name "VDD") (class "Default")
      (node (ref "C13") (pin "1") (pinfunction "1_1") (pintype "passive"))
      (node (ref "C19") (pin "2") (pinfunction "2_2") (pintype "passive"))
      (node (ref "C22") (pin "2") (pinfunction "2_2") (pintype "passive"))
      (node (ref "C23") (pin "2") (pinfunction "2_2") (pintype "passive"))
      (node (ref "C6") (pin "2") (pinfunction "2_2") (pintype "passive"))
      (node (ref "C8") (pin "1") (pinfunction "1_1") (pintype "passive"))
      (node (ref "D4") (pin "2") (pinfunction "K_2") (pintype "passive"))
      (node (ref "P13") (pin "7") (pinfunction "7_7") (pintype "passive"))
      (node (ref "P13") (pin "8") (pinfunction "8_8") (pintype "passive"))
      (node (ref "R1") (pin "1") (pintype "passive"))
      (node (ref "R2") (pin "1") (pintype "passive"))
      (node (ref "R23") (pin "1") (pintype "passive"))
      (node (ref "R4") (pin "1") (pintype "passive"))
      (node (ref "R6") (pin "2") (pinfunction "2_2") (pintype "passive"))
      (node (ref "U2") (pin "100") (pinfunction "VDD_100") (pintype "power_in"))
      (node (ref "U2") (pin "11") (pinfunction "VDD_11") (pintype "power_in"))
      (node (ref "U2") (pin "28") (pinfunction "VDD_28") (pintype "power_in"))
      (node (ref "U2") (pin "46") (pinfunction "VDD_46") (pintype "power_in"))
      (node (ref "U2") (pin "75") (pinfunction "VDD_75") (pintype "power_in"))
    )
    (net (code "123") (name "unconnected-(D4-A-Pad1)") (class "Default")
      (node (ref "D4") (pin "1") (pinfunction "A_1") (pintype "passive"))
    )
    (net (code "124") (name "unconnected-(P10-Pad7)") (class "Default")
      (node (ref "P10") (pin "7") (pintype "passive"))
    )
    (net (code "125") (name "unconnected-(S1-NO-Pad3)") (class "Default")
      (node (ref "S1") (pin "3") (pinfunction "NO_3") (pintype "passive"))
    )
    (net (code "126") (name "unconnected-(U1-NC.-Pad1)") (class "Default")
      (node (ref "U1") (pin "1") (pinfunction "NC._1") (pintype "passive"))
    )
    (net (code "127") (name "unconnected-(U3-FLAG#-Pad3)") (class "Default")
      (node (ref "U3") (pin "3") (pinfunction "FLAG#_3") (pintype "open_collector+no_connect"))
    )
    (net (code "128") (name "unconnected-(U4-FLAG#-Pad3)") (class "Default")
      (node (ref "U4") (pin "3") (pinfunction "FLAG#_3") (pintype "open_collector+no_connect"))
    )
    (net (code "129") (name "unconnected-(U10-GND-Pad1)") (class "Default")
      (node (ref "U10") (pin "1") (pinfunction "GND_1") (pintype "power_in"))
    )
  )
)
